# can.net
KiCad netlist of a schematic drawn in EAGLE
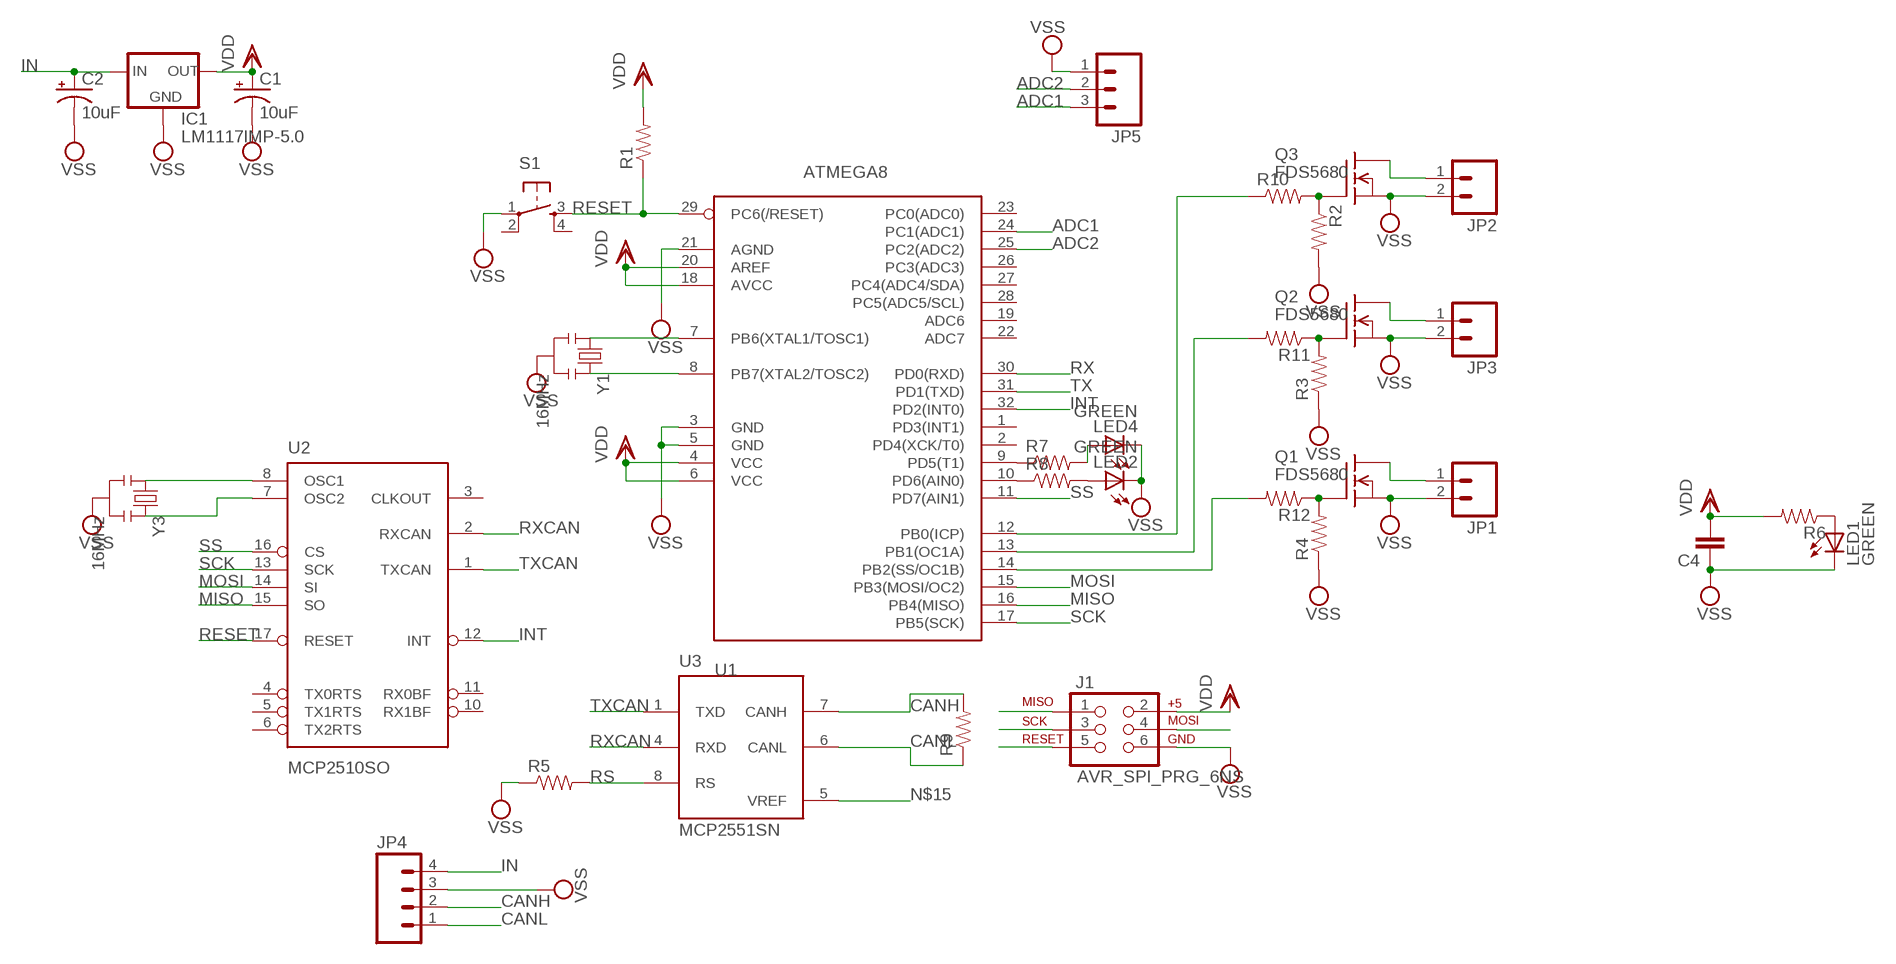
[diagram p0: schematic, sheet 1]

(export (version "E")
  (design (tool "Eeschema 10.0.6"))
  (components
    (comp (ref "C1")
      (value "10uF")
      (footprint "eagle-import:EIA3216")
      (libsource (lib "eagle-import") (part "CAP_POL1206"))
    )
    (comp (ref "C2")
      (value "10uF")
      (footprint "eagle-import:EIA3216")
      (libsource (lib "eagle-import") (part "CAP_POL1206"))
    )
    (comp (ref "C4")
      (value "CAP1206")
      (footprint "eagle-import:1206")
      (libsource (lib "eagle-import") (part "CAP1206"))
    )
    (comp (ref "IC1")
      (value "LM1117IMP-5.0")
      (footprint "eagle-import:SOT223")
      (libsource (lib "eagle-import") (part "LM1117"))
    )
    (comp (ref "J1")
      (value "AVR_SPI_PRG_6NS")
      (footprint "eagle-import:2X3-NS")
      (libsource (lib "eagle-import") (part "AVR_SPI_PRG_6NS"))
    )
    (comp (ref "JP1")
      (value "M02PTH")
      (footprint "eagle-import:1X02")
      (libsource (lib "eagle-import") (part "M02PTH"))
    )
    (comp (ref "JP2")
      (value "M02PTH")
      (footprint "eagle-import:1X02")
      (libsource (lib "eagle-import") (part "M02PTH"))
    )
    (comp (ref "JP3")
      (value "M02PTH")
      (footprint "eagle-import:1X02")
      (libsource (lib "eagle-import") (part "M02PTH"))
    )
    (comp (ref "JP4")
      (value "M041X04_NO_SILK")
      (footprint "eagle-import:1X04_NO_SILK")
      (libsource (lib "eagle-import") (part "M041X04_NO_SILK"))
    )
    (comp (ref "JP5")
      (value "M03PTH")
      (footprint "eagle-import:1X03")
      (libsource (lib "eagle-import") (part "M03PTH"))
    )
    (comp (ref "LED1")
      (value "GREEN")
      (footprint "eagle-import:LED-1206")
      (libsource (lib "eagle-import") (part "LED1206"))
    )
    (comp (ref "LED2")
      (value "GREEN")
      (footprint "eagle-import:LED-1206")
      (libsource (lib "eagle-import") (part "LED1206"))
    )
    (comp (ref "LED4")
      (value "GREEN")
      (footprint "eagle-import:LED-1206")
      (libsource (lib "eagle-import") (part "LED1206"))
    )
    (comp (ref "Q1")
      (value "FDS5680")
      (footprint "eagle-import:SO-8")
      (libsource (lib "eagle-import") (part "FDS5680"))
    )
    (comp (ref "Q2")
      (value "FDS5680")
      (footprint "eagle-import:SO-8")
      (libsource (lib "eagle-import") (part "FDS5680"))
    )
    (comp (ref "Q3")
      (value "FDS5680")
      (footprint "eagle-import:SO-8")
      (libsource (lib "eagle-import") (part "FDS5680"))
    )
    (comp (ref "R1")
      (value "RESISTOR1206")
      (footprint "eagle-import:1206")
      (libsource (lib "eagle-import") (part "SparkFun-Resistors_RESISTOR1206"))
    )
    (comp (ref "R2")
      (value "RESISTOR1206")
      (footprint "eagle-import:1206")
      (libsource (lib "eagle-import") (part "SparkFun-Resistors_RESISTOR1206"))
    )
    (comp (ref "R3")
      (value "RESISTOR1206")
      (footprint "eagle-import:1206")
      (libsource (lib "eagle-import") (part "SparkFun-Resistors_RESISTOR1206"))
    )
    (comp (ref "R4")
      (value "RESISTOR1206")
      (footprint "eagle-import:1206")
      (libsource (lib "eagle-import") (part "SparkFun-Resistors_RESISTOR1206"))
    )
    (comp (ref "R5")
      (value "RESISTOR1206")
      (footprint "eagle-import:1206")
      (libsource (lib "eagle-import") (part "SparkFun-Resistors_RESISTOR1206"))
    )
    (comp (ref "R6")
      (value "RESISTOR1206")
      (footprint "eagle-import:1206")
      (libsource (lib "eagle-import") (part "RESISTOR1206"))
    )
    (comp (ref "R7")
      (value "RESISTOR0805-RES")
      (footprint "eagle-import:0805")
      (libsource (lib "eagle-import") (part "SparkFun-Resistors_RESISTOR0805-RES"))
    )
    (comp (ref "R8")
      (value "RESISTOR0805-RES")
      (footprint "eagle-import:0805")
      (libsource (lib "eagle-import") (part "SparkFun-Resistors_RESISTOR0805-RES"))
    )
    (comp (ref "R9")
      (value "RESISTOR1206")
      (footprint "eagle-import:1206")
      (libsource (lib "eagle-import") (part "SparkFun-Resistors_RESISTOR1206"))
    )
    (comp (ref "R10")
      (value "RESISTOR1206")
      (footprint "eagle-import:1206")
      (libsource (lib "eagle-import") (part "SparkFun-Resistors_RESISTOR1206"))
    )
    (comp (ref "R11")
      (value "RESISTOR1206")
      (footprint "eagle-import:1206")
      (libsource (lib "eagle-import") (part "SparkFun-Resistors_RESISTOR1206"))
    )
    (comp (ref "R12")
      (value "RESISTOR1206")
      (footprint "eagle-import:1206")
      (libsource (lib "eagle-import") (part "SparkFun-Resistors_RESISTOR1206"))
    )
    (comp (ref "S1")
      (value "TAC_SWITCHSMD")
      (footprint "eagle-import:TACTILE_SWITCH_SMD")
      (libsource (lib "eagle-import") (part "TAC_SWITCHSMD"))
    )
    (comp (ref "U1")
      (value "ATMEGA8")
      (footprint "eagle-import:TQFP32-08")
      (libsource (lib "eagle-import") (part "MEGA8-AI"))
    )
    (comp (ref "U2")
      (value "MCP2510SO")
      (footprint "eagle-import:SO-18W")
      (libsource (lib "eagle-import") (part "MCP2510SO"))
    )
    (comp (ref "U3")
      (value "MCP2551SN")
      (footprint "eagle-import:SO-08")
      (libsource (lib "eagle-import") (part "MCP2551SN"))
    )
    (comp (ref "Y1")
      (value "16MHz")
      (footprint "eagle-import:RESONATOR-SMD")
      (libsource (lib "eagle-import") (part "RESONATOR16MHZ"))
    )
    (comp (ref "Y3")
      (value "16MHz")
      (footprint "eagle-import:RESONATOR-SMD")
      (libsource (lib "eagle-import") (part "RESONATOR16MHZ"))
    )
  )
  (nets
    (net (code "1") (name "/ADC1") (class "Default")
      (node (ref "JP5") (pin "3") (pinfunction "3_3") (pintype "passive"))
      (node (ref "U1") (pin "24") (pinfunction "PC1(ADC1)_24") (pintype "bidirectional"))
    )
    (net (code "2") (name "/ADC2") (class "Default")
      (node (ref "JP5") (pin "2") (pinfunction "2_2") (pintype "passive"))
      (node (ref "U1") (pin "25") (pinfunction "PC2(ADC2)_25") (pintype "bidirectional"))
    )
    (net (code "3") (name "/CANH") (class "Default")
      (node (ref "JP4") (pin "2") (pinfunction "2_2") (pintype "passive"))
      (node (ref "R9") (pin "2") (pinfunction "2_2") (pintype "passive"))
      (node (ref "U3") (pin "7") (pinfunction "CANH_7") (pintype "bidirectional"))
    )
    (net (code "4") (name "/CANL") (class "Default")
      (node (ref "JP4") (pin "1") (pinfunction "1_1") (pintype "passive"))
      (node (ref "R9") (pin "1") (pinfunction "1_1") (pintype "passive"))
      (node (ref "U3") (pin "6") (pinfunction "CANL_6") (pintype "bidirectional"))
    )
    (net (code "5") (name "/IN") (class "Default")
      (node (ref "C2") (pin "A") (pinfunction "+_A") (pintype "passive"))
      (node (ref "IC1") (pin "3") (pinfunction "IN_3") (pintype "input"))
      (node (ref "JP4") (pin "4") (pinfunction "4_4") (pintype "passive"))
    )
    (net (code "6") (name "/INT") (class "Default")
      (node (ref "U1") (pin "32") (pinfunction "PD2(INT0)_32") (pintype "bidirectional"))
      (node (ref "U2") (pin "12") (pinfunction "INT_12") (pintype "output"))
    )
    (net (code "7") (name "/MISO") (class "Default")
      (node (ref "J1") (pin "1") (pinfunction "1_1") (pintype "passive"))
      (node (ref "U1") (pin "16") (pinfunction "PB4(MISO)_16") (pintype "bidirectional"))
      (node (ref "U2") (pin "15") (pinfunction "SO_15") (pintype "output"))
    )
    (net (code "8") (name "/MOSI") (class "Default")
      (node (ref "J1") (pin "4") (pinfunction "4_4") (pintype "passive"))
      (node (ref "U1") (pin "15") (pinfunction "PB3(MOSI/OC2)_15") (pintype "bidirectional"))
      (node (ref "U2") (pin "14") (pinfunction "SI_14") (pintype "input"))
    )
    (net (code "9") (name "/N$15") (class "Default")
      (node (ref "U3") (pin "5") (pinfunction "VREF_5") (pintype "power_in"))
    )
    (net (code "10") (name "/RESET") (class "Default")
      (node (ref "J1") (pin "5") (pinfunction "5_5") (pintype "passive"))
      (node (ref "R1") (pin "1") (pinfunction "1_1") (pintype "passive"))
      (node (ref "S1") (pin "3") (pinfunction "3_3") (pintype "passive"))
      (node (ref "U1") (pin "29") (pinfunction "PC6(/RESET)_29") (pintype "bidirectional"))
      (node (ref "U2") (pin "17") (pinfunction "RESET_17") (pintype "input"))
    )
    (net (code "11") (name "/RS") (class "Default")
      (node (ref "R5") (pin "2") (pinfunction "2_2") (pintype "passive"))
      (node (ref "U3") (pin "8") (pinfunction "RS_8") (pintype "input"))
    )
    (net (code "12") (name "/RX") (class "Default")
      (node (ref "U1") (pin "30") (pinfunction "PD0(RXD)_30") (pintype "bidirectional"))
    )
    (net (code "13") (name "/RXCAN") (class "Default")
      (node (ref "U2") (pin "2") (pinfunction "RXCAN_2") (pintype "input"))
      (node (ref "U3") (pin "4") (pinfunction "RXD_4") (pintype "output"))
    )
    (net (code "14") (name "/SCK") (class "Default")
      (node (ref "J1") (pin "3") (pinfunction "3_3") (pintype "passive"))
      (node (ref "U1") (pin "17") (pinfunction "PB5(SCK)_17") (pintype "bidirectional"))
      (node (ref "U2") (pin "13") (pinfunction "SCK_13") (pintype "input"))
    )
    (net (code "15") (name "/SS") (class "Default")
      (node (ref "U1") (pin "11") (pinfunction "PD7(AIN1)_11") (pintype "bidirectional"))
      (node (ref "U2") (pin "16") (pinfunction "CS_16") (pintype "input"))
    )
    (net (code "16") (name "/TX") (class "Default")
      (node (ref "U1") (pin "31") (pinfunction "PD1(TXD)_31") (pintype "bidirectional"))
    )
    (net (code "17") (name "/TXCAN") (class "Default")
      (node (ref "U2") (pin "1") (pinfunction "TXCAN_1") (pintype "output"))
      (node (ref "U3") (pin "1") (pinfunction "TXD_1") (pintype "input"))
    )
    (net (code "18") (name "Net-(JP1-Pad1)") (class "Default")
      (node (ref "JP1") (pin "1") (pinfunction "1_1") (pintype "passive"))
      (node (ref "Q1") (pin "5") (pinfunction "D_5") (pintype "passive"))
      (node (ref "Q1") (pin "6") (pinfunction "D_6") (pintype "passive"))
      (node (ref "Q1") (pin "7") (pinfunction "D_7") (pintype "passive"))
      (node (ref "Q1") (pin "8") (pinfunction "D_8") (pintype "passive"))
    )
    (net (code "19") (name "Net-(JP2-Pad1)") (class "Default")
      (node (ref "JP2") (pin "1") (pinfunction "1_1") (pintype "passive"))
      (node (ref "Q3") (pin "5") (pinfunction "D_5") (pintype "passive"))
      (node (ref "Q3") (pin "6") (pinfunction "D_6") (pintype "passive"))
      (node (ref "Q3") (pin "7") (pinfunction "D_7") (pintype "passive"))
      (node (ref "Q3") (pin "8") (pinfunction "D_8") (pintype "passive"))
    )
    (net (code "20") (name "Net-(JP3-Pad1)") (class "Default")
      (node (ref "JP3") (pin "1") (pinfunction "1_1") (pintype "passive"))
      (node (ref "Q2") (pin "5") (pinfunction "D_5") (pintype "passive"))
      (node (ref "Q2") (pin "6") (pinfunction "D_6") (pintype "passive"))
      (node (ref "Q2") (pin "7") (pinfunction "D_7") (pintype "passive"))
      (node (ref "Q2") (pin "8") (pinfunction "D_8") (pintype "passive"))
    )
    (net (code "21") (name "Net-(LED1-PadA)") (class "Default")
      (node (ref "LED1") (pin "A") (pinfunction "A_A") (pintype "passive"))
      (node (ref "R6") (pin "1") (pinfunction "1_1") (pintype "passive"))
    )
    (net (code "22") (name "Net-(LED2-PadA)") (class "Default")
      (node (ref "LED2") (pin "A") (pinfunction "A_A") (pintype "passive"))
      (node (ref "R8") (pin "2") (pinfunction "2_2") (pintype "passive"))
    )
    (net (code "23") (name "Net-(LED4-PadA)") (class "Default")
      (node (ref "LED4") (pin "A") (pinfunction "A_A") (pintype "passive"))
      (node (ref "R7") (pin "2") (pinfunction "2_2") (pintype "passive"))
    )
    (net (code "24") (name "Net-(Q1-G)") (class "Default")
      (node (ref "Q1") (pin "4") (pinfunction "G_4") (pintype "passive"))
      (node (ref "R12") (pin "1") (pinfunction "1_1") (pintype "passive"))
      (node (ref "R4") (pin "2") (pinfunction "2_2") (pintype "passive"))
    )
    (net (code "25") (name "Net-(Q2-G)") (class "Default")
      (node (ref "Q2") (pin "4") (pinfunction "G_4") (pintype "passive"))
      (node (ref "R11") (pin "1") (pinfunction "1_1") (pintype "passive"))
      (node (ref "R3") (pin "2") (pinfunction "2_2") (pintype "passive"))
    )
    (net (code "26") (name "Net-(Q3-G)") (class "Default")
      (node (ref "Q3") (pin "4") (pinfunction "G_4") (pintype "passive"))
      (node (ref "R10") (pin "2") (pinfunction "2_2") (pintype "passive"))
      (node (ref "R2") (pin "1") (pinfunction "1_1") (pintype "passive"))
    )
    (net (code "27") (name "Net-(U1-PB0(ICP))") (class "Default")
      (node (ref "R10") (pin "1") (pinfunction "1_1") (pintype "passive"))
      (node (ref "U1") (pin "12") (pinfunction "PB0(ICP)_12") (pintype "bidirectional"))
    )
    (net (code "28") (name "Net-(U1-PB1(OC1A))") (class "Default")
      (node (ref "R11") (pin "2") (pinfunction "2_2") (pintype "passive"))
      (node (ref "U1") (pin "13") (pinfunction "PB1(OC1A)_13") (pintype "bidirectional"))
    )
    (net (code "29") (name "Net-(U1-PB2(SS{slash}OC1B))") (class "Default")
      (node (ref "R12") (pin "2") (pinfunction "2_2") (pintype "passive"))
      (node (ref "U1") (pin "14") (pinfunction "PB2(SS/OC1B)_14") (pintype "bidirectional"))
    )
    (net (code "30") (name "Net-(U1-PB6(XTAL1{slash}TOSC1))") (class "Default")
      (node (ref "U1") (pin "7") (pinfunction "PB6(XTAL1/TOSC1)_7") (pintype "bidirectional"))
      (node (ref "Y1") (pin "1") (pinfunction "1_1") (pintype "passive"))
    )
    (net (code "31") (name "Net-(U1-PB7(XTAL2{slash}TOSC2))") (class "Default")
      (node (ref "U1") (pin "8") (pinfunction "PB7(XTAL2/TOSC2)_8") (pintype "bidirectional"))
      (node (ref "Y1") (pin "3") (pinfunction "3_3") (pintype "passive"))
    )
    (net (code "32") (name "Net-(U1-PD5(T1))") (class "Default")
      (node (ref "R7") (pin "1") (pinfunction "1_1") (pintype "passive"))
      (node (ref "U1") (pin "9") (pinfunction "PD5(T1)_9") (pintype "bidirectional"))
    )
    (net (code "33") (name "Net-(U1-PD6(AIN0))") (class "Default")
      (node (ref "R8") (pin "1") (pinfunction "1_1") (pintype "passive"))
      (node (ref "U1") (pin "10") (pinfunction "PD6(AIN0)_10") (pintype "bidirectional"))
    )
    (net (code "34") (name "Net-(U2A-OSC1)") (class "Default")
      (node (ref "U2") (pin "8") (pinfunction "OSC1_8") (pintype "input"))
      (node (ref "Y3") (pin "1") (pinfunction "1_1") (pintype "passive"))
    )
    (net (code "35") (name "Net-(U2A-OSC2)") (class "Default")
      (node (ref "U2") (pin "7") (pinfunction "OSC2_7") (pintype "output"))
      (node (ref "Y3") (pin "3") (pinfunction "3_3") (pintype "passive"))
    )
    (net (code "36") (name "VDD") (class "Default")
      (node (ref "C1") (pin "A") (pinfunction "+_A") (pintype "passive"))
      (node (ref "C4") (pin "2") (pinfunction "2_2") (pintype "passive"))
      (node (ref "IC1") (pin "2") (pinfunction "OUT_2") (pintype "passive"))
      (node (ref "J1") (pin "2") (pinfunction "2_2") (pintype "passive"))
      (node (ref "R1") (pin "2") (pinfunction "2_2") (pintype "passive"))
      (node (ref "R6") (pin "2") (pinfunction "2_2") (pintype "passive"))
      (node (ref "U1") (pin "18") (pinfunction "AVCC_18") (pintype "bidirectional"))
      (node (ref "U1") (pin "20") (pinfunction "AREF_20") (pintype "bidirectional"))
      (node (ref "U1") (pin "4") (pinfunction "VCC_4") (pintype "bidirectional"))
      (node (ref "U1") (pin "6") (pinfunction "VCC_6") (pintype "bidirectional"))
    )
    (net (code "37") (name "VSS") (class "Default")
      (node (ref "C1") (pin "C") (pinfunction "-_C") (pintype "passive"))
      (node (ref "C2") (pin "C") (pinfunction "-_C") (pintype "passive"))
      (node (ref "C4") (pin "1") (pinfunction "1_1") (pintype "passive"))
      (node (ref "IC1") (pin "1") (pinfunction "GND_1") (pintype "input"))
      (node (ref "J1") (pin "6") (pinfunction "6_6") (pintype "passive"))
      (node (ref "JP1") (pin "2") (pinfunction "2_2") (pintype "passive"))
      (node (ref "JP2") (pin "2") (pinfunction "2_2") (pintype "passive"))
      (node (ref "JP3") (pin "2") (pinfunction "2_2") (pintype "passive"))
      (node (ref "JP4") (pin "3") (pinfunction "3_3") (pintype "passive"))
      (node (ref "JP5") (pin "1") (pinfunction "1_1") (pintype "passive"))
      (node (ref "LED1") (pin "C") (pinfunction "C_C") (pintype "passive"))
      (node (ref "LED2") (pin "C") (pinfunction "C_C") (pintype "passive"))
      (node (ref "LED4") (pin "C") (pinfunction "C_C") (pintype "passive"))
      (node (ref "Q1") (pin "1") (pinfunction "S_1") (pintype "passive"))
      (node (ref "Q1") (pin "2") (pinfunction "S_2") (pintype "passive"))
      (node (ref "Q1") (pin "3") (pinfunction "S_3") (pintype "passive"))
      (node (ref "Q2") (pin "1") (pinfunction "S_1") (pintype "passive"))
      (node (ref "Q2") (pin "2") (pinfunction "S_2") (pintype "passive"))
      (node (ref "Q2") (pin "3") (pinfunction "S_3") (pintype "passive"))
      (node (ref "Q3") (pin "1") (pinfunction "S_1") (pintype "passive"))
      (node (ref "Q3") (pin "2") (pinfunction "S_2") (pintype "passive"))
      (node (ref "Q3") (pin "3") (pinfunction "S_3") (pintype "passive"))
      (node (ref "R2") (pin "2") (pinfunction "2_2") (pintype "passive"))
      (node (ref "R3") (pin "1") (pinfunction "1_1") (pintype "passive"))
      (node (ref "R4") (pin "1") (pinfunction "1_1") (pintype "passive"))
      (node (ref "R5") (pin "1") (pinfunction "1_1") (pintype "passive"))
      (node (ref "S1") (pin "1") (pinfunction "1_1") (pintype "passive"))
      (node (ref "U1") (pin "21") (pinfunction "AGND_21") (pintype "bidirectional"))
      (node (ref "U1") (pin "3") (pinfunction "GND_3") (pintype "bidirectional"))
      (node (ref "U1") (pin "5") (pinfunction "GND_5") (pintype "bidirectional"))
      (node (ref "Y1") (pin "2") (pinfunction "2_2") (pintype "passive"))
      (node (ref "Y3") (pin "2") (pinfunction "2_2") (pintype "passive"))
    )
    (net (code "38") (name "unconnected-(S1-Pad2)") (class "Default")
      (node (ref "S1") (pin "2") (pinfunction "2_2") (pintype "passive"))
    )
    (net (code "39") (name "unconnected-(S1-Pad4)") (class "Default")
      (node (ref "S1") (pin "4") (pinfunction "4_4") (pintype "passive"))
    )
    (net (code "40") (name "unconnected-(U1-ADC6-Pad19)") (class "Default")
      (node (ref "U1") (pin "19") (pinfunction "ADC6_19") (pintype "bidirectional"))
    )
    (net (code "41") (name "unconnected-(U1-ADC7-Pad22)") (class "Default")
      (node (ref "U1") (pin "22") (pinfunction "ADC7_22") (pintype "bidirectional"))
    )
    (net (code "42") (name "unconnected-(U1-PC0(ADC0)-Pad23)") (class "Default")
      (node (ref "U1") (pin "23") (pinfunction "PC0(ADC0)_23") (pintype "bidirectional"))
    )
    (net (code "43") (name "unconnected-(U1-PC3(ADC3)-Pad26)") (class "Default")
      (node (ref "U1") (pin "26") (pinfunction "PC3(ADC3)_26") (pintype "bidirectional"))
    )
    (net (code "44") (name "unconnected-(U1-PC4(ADC4{slash}SDA)-Pad27)") (class "Default")
      (node (ref "U1") (pin "27") (pinfunction "PC4(ADC4/SDA)_27") (pintype "bidirectional"))
    )
    (net (code "45") (name "unconnected-(U1-PC5(ADC5{slash}SCL)-Pad28)") (class "Default")
      (node (ref "U1") (pin "28") (pinfunction "PC5(ADC5/SCL)_28") (pintype "bidirectional"))
    )
    (net (code "46") (name "unconnected-(U1-PD3(INT1)-Pad1)") (class "Default")
      (node (ref "U1") (pin "1") (pinfunction "PD3(INT1)_1") (pintype "bidirectional"))
    )
    (net (code "47") (name "unconnected-(U1-PD4(XCK{slash}T0)-Pad2)") (class "Default")
      (node (ref "U1") (pin "2") (pinfunction "PD4(XCK/T0)_2") (pintype "bidirectional"))
    )
    (net (code "48") (name "unconnected-(U2A-CLKOUT-Pad3)") (class "Default")
      (node (ref "U2") (pin "3") (pinfunction "CLKOUT_3") (pintype "output"))
    )
    (net (code "49") (name "unconnected-(U2A-RX0BF-Pad11)") (class "Default")
      (node (ref "U2") (pin "11") (pinfunction "RX0BF_11") (pintype "output"))
    )
    (net (code "50") (name "unconnected-(U2A-RX1BF-Pad10)") (class "Default")
      (node (ref "U2") (pin "10") (pinfunction "RX1BF_10") (pintype "output"))
    )
    (net (code "51") (name "unconnected-(U2A-TX0RTS-Pad4)") (class "Default")
      (node (ref "U2") (pin "4") (pinfunction "TX0RTS_4") (pintype "input"))
    )
    (net (code "52") (name "unconnected-(U2A-TX1RTS-Pad5)") (class "Default")
      (node (ref "U2") (pin "5") (pinfunction "TX1RTS_5") (pintype "input"))
    )
    (net (code "53") (name "unconnected-(U2A-TX2RTS-Pad6)") (class "Default")
      (node (ref "U2") (pin "6") (pinfunction "TX2RTS_6") (pintype "input"))
    )
  )
)
